# STM32.net
KiCad netlist of a schematic drawn in Altium Designer
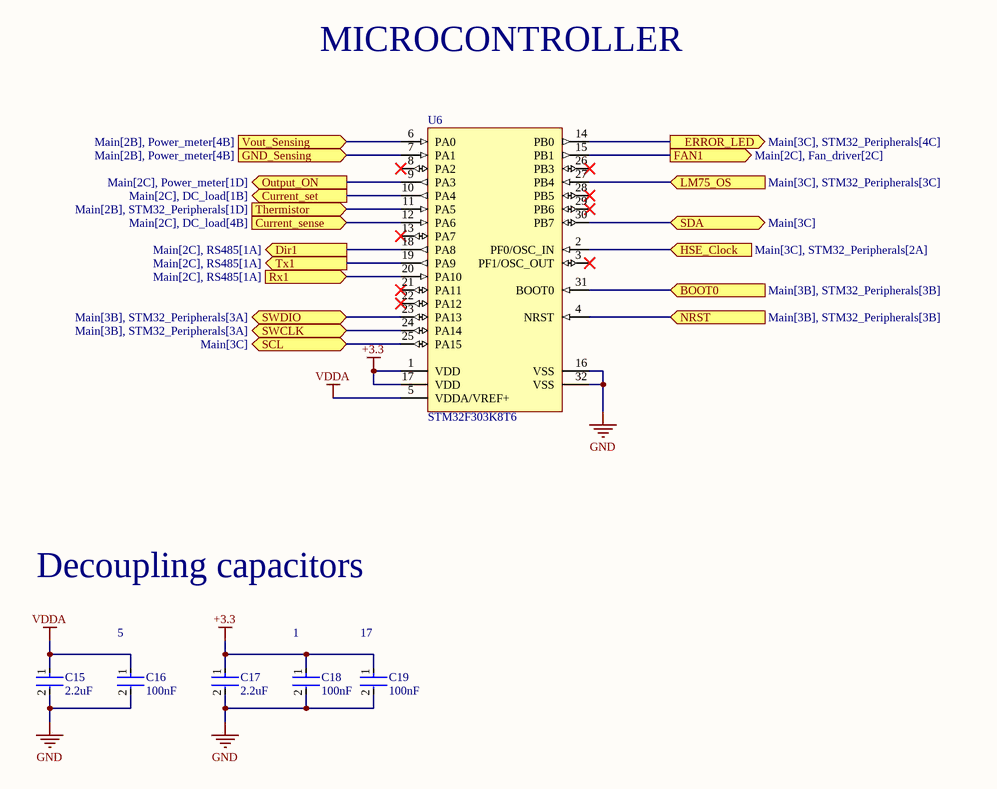
[diagram p0: STM32.SchDoc]

(export (version "E")
  (design (tool "Eeschema 10.0.6"))
  (components
    (comp (ref "C15")
      (value "2.2uF")
      (footprint "FP-0805-L_2_01_0_2-W_1_25-IPC_B")
      (description "General Purpose Ceramic Capacitor, 0805, 10nF, 10%, X7R, 15%, 100V")
      (fields (field (name "VOLTAGE") "100V") (field (name "TOLERANCE") "10%"))
      (libsource (lib "Altium Content Vault") (part "b4654b650e69147ec39a6b967a45e02"))
    )
    (comp (ref "C16")
      (value "100nF")
      (footprint "FP-CGA3E-0_3-0_1-IPC_A")
      (description "Cap Ceramic 100nF 50V X7R 10% Pad SMD 0603 +125°C Automotive T/R")
      (fields (field (name "TOLERANCE") "10%") (field (name "VOLTAGE") "50V"))
      (libsource (lib "Altium Content Vault") (part "b4654b650e69147ec39a6b967a45e02"))
    )
    (comp (ref "C17")
      (value "2.2uF")
      (footprint "FP-0805-L_2_01_0_2-W_1_25-IPC_B")
      (description "General Purpose Ceramic Capacitor, 0805, 10nF, 10%, X7R, 15%, 100V")
      (fields (field (name "VOLTAGE") "100V") (field (name "TOLERANCE") "10%"))
      (libsource (lib "Altium Content Vault") (part "b4654b650e69147ec39a6b967a45e02"))
    )
    (comp (ref "C18")
      (value "100nF")
      (footprint "FP-CGA3E-0_3-0_1-IPC_A")
      (description "Cap Ceramic 100nF 50V X7R 10% Pad SMD 0603 +125°C Automotive T/R")
      (fields (field (name "TOLERANCE") "10%") (field (name "VOLTAGE") "50V"))
      (libsource (lib "Altium Content Vault") (part "b4654b650e69147ec39a6b967a45e02"))
    )
    (comp (ref "C19")
      (value "100nF")
      (footprint "FP-CGA3E-0_3-0_1-IPC_A")
      (description "Cap Ceramic 100nF 50V X7R 10% Pad SMD 0603 +125°C Automotive T/R")
      (fields (field (name "TOLERANCE") "10%") (field (name "VOLTAGE") "50V"))
      (libsource (lib "Altium Content Vault") (part "b4654b650e69147ec39a6b967a45e02"))
    )
    (comp (ref "U6")
      (value "STM32F303K8T6")
      (footprint "STM-LQFP32_M")
      (libsource (lib "Altium Content Vault") (part "MC-ARM-STM32F303-LQFP32"))
    )
  )
  (nets
    (net (code "1") (name "+3.3") (class "Default")
      (node (ref "C17") (pin "1") (pinfunction "1_1") (pintype "passive"))
      (node (ref "C18") (pin "1") (pinfunction "1_1") (pintype "passive"))
      (node (ref "C19") (pin "1") (pinfunction "1_1") (pintype "passive"))
      (node (ref "U6") (pin "1") (pinfunction "VDD_1") (pintype "power_in"))
      (node (ref "U6") (pin "17") (pinfunction "VDD_17") (pintype "power_in"))
    )
    (net (code "2") (name "/BOOT0") (class "Default")
      (node (ref "U6") (pin "31") (pinfunction "BOOT0_31") (pintype "input"))
    )
    (net (code "3") (name "/Current_sense") (class "Default")
      (node (ref "U6") (pin "12") (pinfunction "PA6_12") (pintype "input"))
    )
    (net (code "4") (name "/Current_set") (class "Default")
      (node (ref "U6") (pin "10") (pinfunction "PA4_10") (pintype "output"))
    )
    (net (code "5") (name "/Dir1") (class "Default")
      (node (ref "U6") (pin "18") (pinfunction "PA8_18") (pintype "output"))
    )
    (net (code "6") (name "/ERROR_LED") (class "Default")
      (node (ref "U6") (pin "14") (pinfunction "PB0_14") (pintype "output"))
    )
    (net (code "7") (name "/FAN1") (class "Default")
      (node (ref "U6") (pin "15") (pinfunction "PB1_15") (pintype "output"))
    )
    (net (code "8") (name "/GND_Sensing") (class "Default")
      (node (ref "U6") (pin "7") (pinfunction "PA1_7") (pintype "input"))
    )
    (net (code "9") (name "/HSE_Clock") (class "Default")
      (node (ref "U6") (pin "2") (pinfunction "PF0/OSC_IN_2") (pintype "input"))
    )
    (net (code "10") (name "/LM75_OS") (class "Default")
      (node (ref "U6") (pin "27") (pinfunction "PB4_27") (pintype "input"))
    )
    (net (code "11") (name "/NRST") (class "Default")
      (node (ref "U6") (pin "4") (pinfunction "NRST_4") (pintype "input"))
    )
    (net (code "12") (name "/Output_ON") (class "Default")
      (node (ref "U6") (pin "9") (pinfunction "PA3_9") (pintype "output"))
    )
    (net (code "13") (name "/Rx1") (class "Default")
      (node (ref "U6") (pin "20") (pinfunction "PA10_20") (pintype "input"))
    )
    (net (code "14") (name "/SCL") (class "Default")
      (node (ref "U6") (pin "25") (pinfunction "PA15_25") (pintype "bidirectional"))
    )
    (net (code "15") (name "/SDA") (class "Default")
      (node (ref "U6") (pin "30") (pinfunction "PB7_30") (pintype "bidirectional"))
    )
    (net (code "16") (name "/SWCLK") (class "Default")
      (node (ref "U6") (pin "24") (pinfunction "PA14_24") (pintype "bidirectional"))
    )
    (net (code "17") (name "/SWDIO") (class "Default")
      (node (ref "U6") (pin "23") (pinfunction "PA13_23") (pintype "bidirectional"))
    )
    (net (code "18") (name "/Thermistor") (class "Default")
      (node (ref "U6") (pin "11") (pinfunction "PA5_11") (pintype "input"))
    )
    (net (code "19") (name "/Tx1") (class "Default")
      (node (ref "U6") (pin "19") (pinfunction "PA9_19") (pintype "output"))
    )
    (net (code "20") (name "/Vout_Sensing") (class "Default")
      (node (ref "U6") (pin "6") (pinfunction "PA0_6") (pintype "input"))
    )
    (net (code "21") (name "GND") (class "Default")
      (node (ref "C15") (pin "2") (pinfunction "2_2") (pintype "passive"))
      (node (ref "C16") (pin "2") (pinfunction "2_2") (pintype "passive"))
      (node (ref "C17") (pin "2") (pinfunction "2_2") (pintype "passive"))
      (node (ref "C18") (pin "2") (pinfunction "2_2") (pintype "passive"))
      (node (ref "C19") (pin "2") (pinfunction "2_2") (pintype "passive"))
      (node (ref "U6") (pin "16") (pinfunction "VSS_16") (pintype "power_in"))
      (node (ref "U6") (pin "32") (pinfunction "VSS_32") (pintype "power_in"))
    )
    (net (code "22") (name "VDDA") (class "Default")
      (node (ref "C15") (pin "1") (pinfunction "1_1") (pintype "passive"))
      (node (ref "C16") (pin "1") (pinfunction "1_1") (pintype "passive"))
      (node (ref "U6") (pin "5") (pinfunction "VDDA/VREF+_5") (pintype "power_in"))
    )
    (net (code "23") (name "unconnected-(U6-PA2-Pad8)") (class "Default")
      (node (ref "U6") (pin "8") (pinfunction "PA2_8") (pintype "bidirectional+no_connect"))
    )
    (net (code "24") (name "unconnected-(U6-PA7-Pad13)") (class "Default")
      (node (ref "U6") (pin "13") (pinfunction "PA7_13") (pintype "bidirectional+no_connect"))
    )
    (net (code "25") (name "unconnected-(U6-PA11-Pad21)") (class "Default")
      (node (ref "U6") (pin "21") (pinfunction "PA11_21") (pintype "bidirectional+no_connect"))
    )
    (net (code "26") (name "unconnected-(U6-PA12-Pad22)") (class "Default")
      (node (ref "U6") (pin "22") (pinfunction "PA12_22") (pintype "bidirectional+no_connect"))
    )
    (net (code "27") (name "unconnected-(U6-PB3-Pad26)") (class "Default")
      (node (ref "U6") (pin "26") (pinfunction "PB3_26") (pintype "bidirectional+no_connect"))
    )
    (net (code "28") (name "unconnected-(U6-PB5-Pad28)") (class "Default")
      (node (ref "U6") (pin "28") (pinfunction "PB5_28") (pintype "bidirectional+no_connect"))
    )
    (net (code "29") (name "unconnected-(U6-PB6-Pad29)") (class "Default")
      (node (ref "U6") (pin "29") (pinfunction "PB6_29") (pintype "bidirectional+no_connect"))
    )
    (net (code "30") (name "unconnected-(U6-PF1{slash}OSC_OUT-Pad3)") (class "Default")
      (node (ref "U6") (pin "3") (pinfunction "PF1/OSC_OUT_3") (pintype "bidirectional+no_connect"))
    )
  )
)
